# rhd_board.net
KiCad netlist of a schematic drawn in Altium Designer
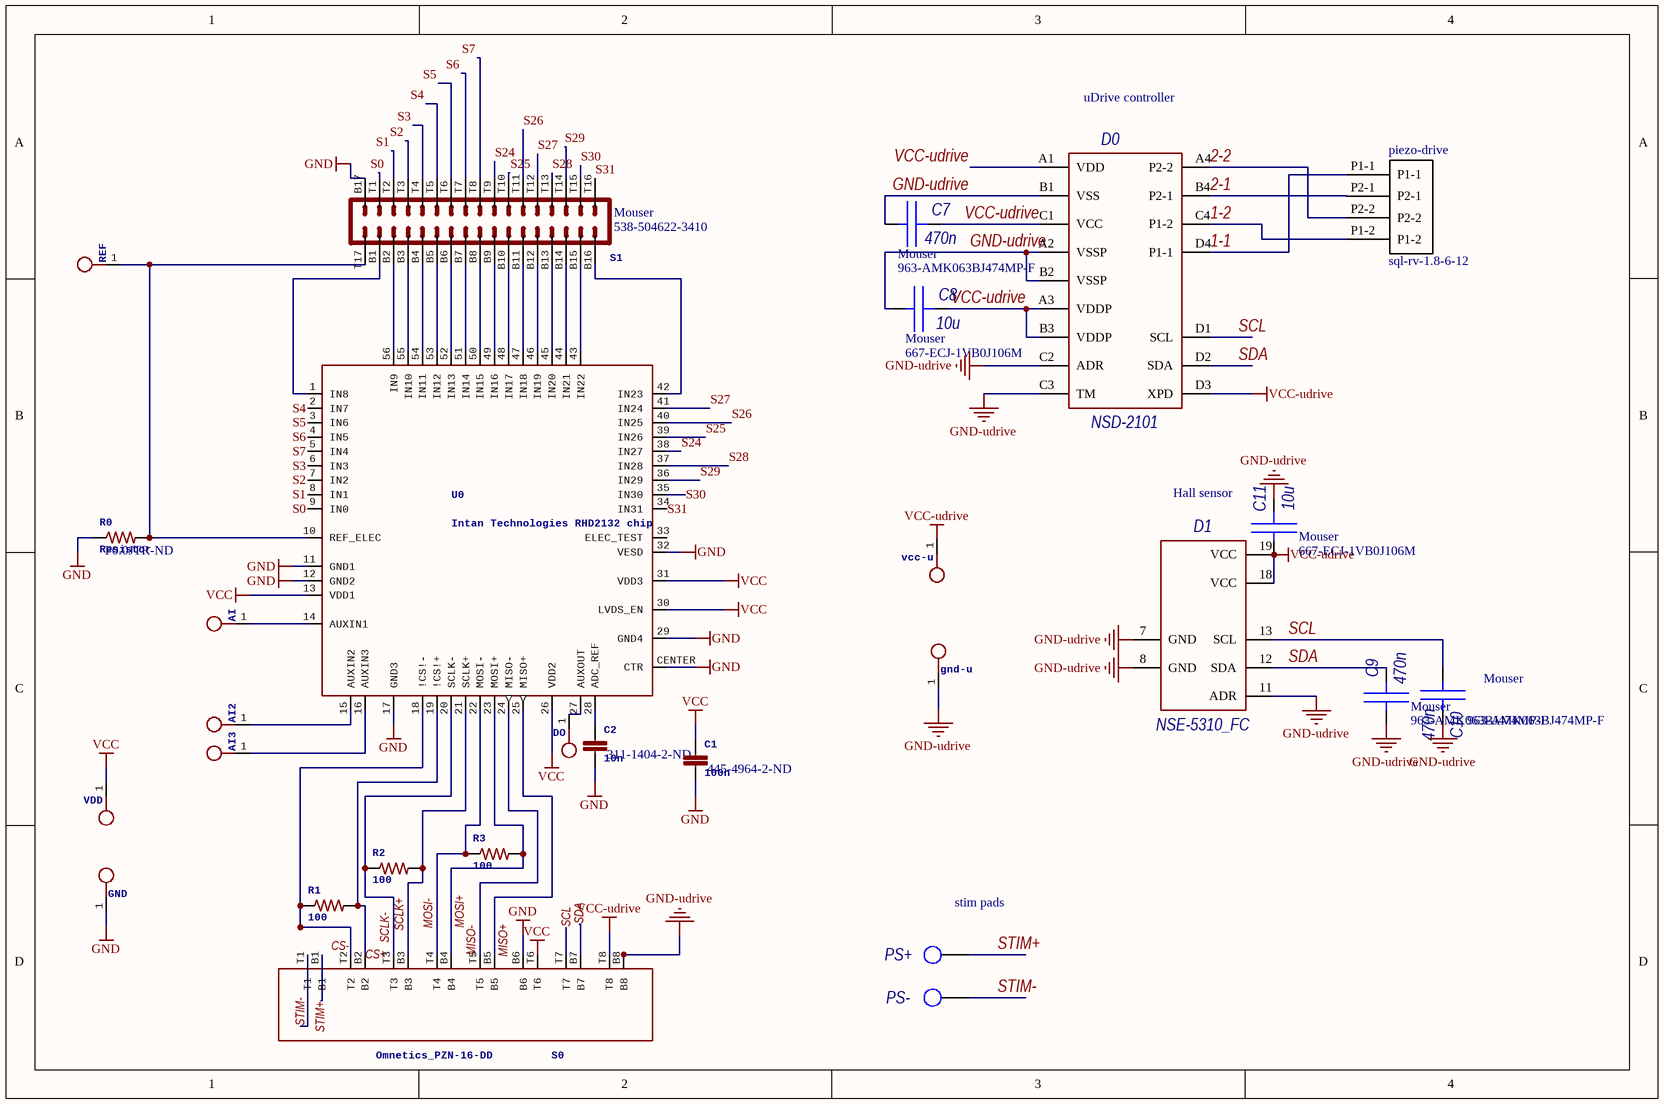
[diagram p0: rhd_board.SchDoc]

(export (version "E")
  (design (tool "Eeschema 10.0.6"))
  (components
    (comp (ref "AI")
      (value "PCB Test Point")
      (footprint "TESTPOINT_SMALL")
      (libsource (lib "RHD2000_eval_board") (part "TESTPOINT_SMALL"))
    )
    (comp (ref "AI2")
      (value "PCB Test Point")
      (footprint "TESTPOINT_SMALL")
      (libsource (lib "RHD2000_eval_board") (part "TESTPOINT_SMALL"))
    )
    (comp (ref "AI3")
      (value "PCB Test Point")
      (footprint "TESTPOINT_SMALL")
      (libsource (lib "RHD2000_eval_board") (part "TESTPOINT_SMALL"))
    )
    (comp (ref "C1")
      (value "100n")
      (footprint "0402")
      (description "ceramic capacitor (25 V). For pwer supply decoupling")
      (fields (field (name "SUPPLIER PART NUMBER 1") "445-4964-2-ND"))
      (libsource (lib "RHD2000_eval_board") (part "C_100nf"))
    )
    (comp (ref "C2")
      (value "10n")
      (footprint "0201")
      (description "ceramic 16v")
      (fields (field (name "SUPPLIER PART NUMBER 1") "311-1404-2-ND"))
      (libsource (lib "RHD2000_eval_board") (part "C_10nF"))
    )
    (comp (ref "C7")
      (value "470n")
      (footprint "CAPC0603X03L")
      (description "Capacitor")
      (fields
        (field (name "SUPPLIER 1") "Mouser")
        (field (name "SUPPLIER PART NUMBER 1") "963-AMK063BJ474MP-F")
        (field (name "PUBLISHER") "RVS")
      )
      (libsource (lib "Microdrive_Drive") (part "Cap-603"))
    )
    (comp (ref "C8")
      (value "10u")
      (footprint "CAPC1608X09L")
      (description "Capacitor")
      (fields
        (field (name "SUPPLIER 1") "Mouser")
        (field (name "SUPPLIER PART NUMBER 1") "667-ECJ-1VB0J106M")
        (field (name "PUBLISHER") "RVS")
      )
      (libsource (lib "Microdrive_Drive") (part "Cap-1608"))
    )
    (comp (ref "C9")
      (value "470n")
      (footprint "CAPC0603X03L")
      (description "Capacitor")
      (fields
        (field (name "SUPPLIER 1") "Mouser")
        (field (name "SUPPLIER PART NUMBER 1") "963-AMK063BJ474MP-F")
        (field (name "PUBLISHER") "RVS")
      )
      (libsource (lib "Microdrive_Drive") (part "Cap-603"))
    )
    (comp (ref "C10")
      (value "470n")
      (footprint "CAPC0603X03L")
      (description "Capacitor")
      (fields
        (field (name "SUPPLIER 1") "Mouser")
        (field (name "SUPPLIER PART NUMBER 1") "963-AMK063BJ474MP-F")
        (field (name "PUBLISHER") "RVS")
      )
      (libsource (lib "Microdrive_Drive") (part "Cap-603"))
    )
    (comp (ref "C11")
      (value "10u")
      (footprint "CAPC1608X09L")
      (description "Capacitor")
      (fields
        (field (name "SUPPLIER 1") "Mouser")
        (field (name "SUPPLIER PART NUMBER 1") "667-ECJ-1VB0J106M")
        (field (name "PUBLISHER") "RVS")
      )
      (libsource (lib "Microdrive_Drive") (part "Cap-1608"))
    )
    (comp (ref "D0")
      (value "NSD-2101")
      (footprint "BGA16C40P4X4_175X175X63")
      (libsource (lib "Microdrive_Drive") (part "NSD-2101"))
    )
    (comp (ref "D1")
      (value "NSE-5310_FC")
      (footprint "NSE-5310_FC")
      (libsource (lib "Microdrive_Drive") (part "NSE-5310_FC"))
    )
    (comp (ref "DO")
      (value "PCB Test Point")
      (footprint "TESTPOINT_SMALL")
      (libsource (lib "RHD2000_eval_board") (part "TESTPOINT_SMALL"))
    )
    (comp (ref "GND")
      (value "PCB Test Point")
      (footprint "TESTPOINT_SMALL")
      (libsource (lib "RHD2000_eval_board") (part "TESTPOINT_SMALL"))
    )
    (comp (ref "gnd-u")
      (value "PCB Test Point")
      (footprint "TESTPOINT_SMALL")
      (libsource (lib "RHD2000_eval_board") (part "TESTPOINT_SMALL"))
    )
    (comp (ref "piezo-drive")
      (value "sql-rv-1.8-6-12")
      (footprint "sql-rv-1.8-6-12")
      (description "Squiggle motor")
      (libsource (lib "Microdrive_Drive") (part "sql-rv-1.8-6-12"))
    )
    (comp (ref "PS+")
      (value "2-2")
      (footprint "KP-025-04")
      (libsource (lib "Microdrive_Drive") (part "KP-025X04"))
    )
    (comp (ref "PS-")
      (value "2-2")
      (footprint "KP-025-04")
      (libsource (lib "Microdrive_Drive") (part "KP-025X04"))
    )
    (comp (ref "R0")
      (value "Resistor")
      (footprint "0402")
      (description "resistor 0ohm")
      (fields (field (name "SUPPLIER PART NUMBER 1") "P0.0JTR-ND"))
      (libsource (lib "RHD2000_eval_board") (part "R_0ohm"))
    )
    (comp (ref "R1")
      (value "100")
      (footprint "0201")
      (description "100ohm resistor for lvds pair in 64ch")
      (libsource (lib "RHD2000_eval_board") (part "R_100_LVDS"))
    )
    (comp (ref "R2")
      (value "100")
      (footprint "0201")
      (description "100ohm resistor for lvds pair in 64ch")
      (libsource (lib "RHD2000_eval_board") (part "R_100_LVDS"))
    )
    (comp (ref "R3")
      (value "100")
      (footprint "0201")
      (description "100ohm resistor for lvds pair in 64ch")
      (libsource (lib "RHD2000_eval_board") (part "R_100_LVDS"))
    )
    (comp (ref "REF")
      (value "PCB Test Point")
      (footprint "TESTPOINT_SMALL")
      (libsource (lib "RHD2000_eval_board") (part "TESTPOINT_SMALL"))
    )
    (comp (ref "S0")
      (value "Omnetics_PZN-16-DD")
      (footprint "OMNETICS_PZN-16-DD")
      (libsource (lib "RHD2000_eval_board") (part "Omnetics_PZN-16-DD"))
    )
    (comp (ref "S1")
      (value "Molex 3.5mm Pitch Slimstack 34 pin connector")
      (footprint "MOLEX_504622-3412")
      (fields (field (name "SUPPLIER 1") "Mouser") (field (name "SUPPLIER PART NUMBER 1") "538-504622-3410"))
      (libsource (lib "Microdrive_Drive") (part "MOLEX_504622-3412"))
    )
    (comp (ref "U0")
      (value "Intan Technologies RHD2132 chip")
      (footprint "RHD2000_56PIN_COB")
      (libsource (lib "RHD2000") (part "RHD2132_COB"))
    )
    (comp (ref "vcc-u")
      (value "PCB Test Point")
      (footprint "TESTPOINT_SMALL")
      (libsource (lib "RHD2000_eval_board") (part "TESTPOINT_SMALL"))
    )
    (comp (ref "VDD")
      (value "PCB Test Point")
      (footprint "TESTPOINT_SMALL")
      (libsource (lib "RHD2000_eval_board") (part "TESTPOINT_SMALL"))
    )
  )
  (nets
    (net (code "1") (name "/1-1") (class "Default")
      (node (ref "D0") (pin "D4") (pinfunction "P1-1_D4") (pintype "passive"))
      (node (ref "piezo-drive") (pin "P1-1") (pinfunction "P1-1_P1-1") (pintype "passive"))
    )
    (net (code "2") (name "/1-2") (class "Default")
      (node (ref "D0") (pin "C4") (pinfunction "P1-2_C4") (pintype "passive"))
      (node (ref "piezo-drive") (pin "P1-2") (pinfunction "P1-2_P1-2") (pintype "passive"))
    )
    (net (code "3") (name "/2-1") (class "Default")
      (node (ref "D0") (pin "B4") (pinfunction "P2-1_B4") (pintype "passive"))
      (node (ref "piezo-drive") (pin "P2-1") (pinfunction "P2-1_P2-1") (pintype "passive"))
    )
    (net (code "4") (name "/2-2") (class "Default")
      (node (ref "D0") (pin "A4") (pinfunction "P2-2_A4") (pintype "passive"))
      (node (ref "piezo-drive") (pin "P2-2") (pinfunction "P2-2_P2-2") (pintype "passive"))
    )
    (net (code "5") (name "/CS+") (class "Default")
      (node (ref "R1") (pin "2") (pinfunction "2_2") (pintype "passive"))
      (node (ref "S0") (pin "B2") (pinfunction "B2_B2") (pintype "passive"))
      (node (ref "U0") (pin "19") (pinfunction "!CS!+_19") (pintype "passive"))
    )
    (net (code "6") (name "/CS-") (class "Default")
      (node (ref "R1") (pin "1") (pinfunction "1_1") (pintype "passive"))
      (node (ref "S0") (pin "T2") (pinfunction "T2_T2") (pintype "passive"))
      (node (ref "U0") (pin "18") (pinfunction "!CS!-_18") (pintype "passive"))
    )
    (net (code "7") (name "/MISO+") (class "Default")
      (node (ref "S0") (pin "B5") (pinfunction "B5_B5") (pintype "passive"))
      (node (ref "U0") (pin "25") (pinfunction "MISO+_25") (pintype "output"))
    )
    (net (code "8") (name "/MISO-") (class "Default")
      (node (ref "S0") (pin "T5") (pinfunction "T5_T5") (pintype "passive"))
      (node (ref "U0") (pin "24") (pinfunction "MISO-_24") (pintype "output"))
    )
    (net (code "9") (name "/MOSI+") (class "Default")
      (node (ref "R3") (pin "2") (pinfunction "2_2") (pintype "passive"))
      (node (ref "S0") (pin "B4") (pinfunction "B4_B4") (pintype "passive"))
      (node (ref "U0") (pin "23") (pinfunction "MOSI+_23") (pintype "passive"))
    )
    (net (code "10") (name "/MOSI-") (class "Default")
      (node (ref "R3") (pin "1") (pinfunction "1_1") (pintype "passive"))
      (node (ref "S0") (pin "T4") (pinfunction "T4_T4") (pintype "passive"))
      (node (ref "U0") (pin "22") (pinfunction "MOSI-_22") (pintype "passive"))
    )
    (net (code "11") (name "/S0") (class "Default")
      (node (ref "S1") (pin "T1") (pinfunction "T1_T1") (pintype "passive"))
      (node (ref "U0") (pin "9") (pinfunction "IN0_9") (pintype "passive"))
    )
    (net (code "12") (name "/S1") (class "Default")
      (node (ref "S1") (pin "T2") (pinfunction "T2_T2") (pintype "passive"))
      (node (ref "U0") (pin "8") (pinfunction "IN1_8") (pintype "passive"))
    )
    (net (code "13") (name "/S2") (class "Default")
      (node (ref "S1") (pin "T3") (pinfunction "T3_T3") (pintype "passive"))
      (node (ref "U0") (pin "7") (pinfunction "IN2_7") (pintype "passive"))
    )
    (net (code "14") (name "/S3") (class "Default")
      (node (ref "S1") (pin "T4") (pinfunction "T4_T4") (pintype "passive"))
      (node (ref "U0") (pin "6") (pinfunction "IN3_6") (pintype "passive"))
    )
    (net (code "15") (name "/S4") (class "Default")
      (node (ref "S1") (pin "T5") (pinfunction "T5_T5") (pintype "passive"))
      (node (ref "U0") (pin "2") (pinfunction "IN7_2") (pintype "passive"))
    )
    (net (code "16") (name "/S5") (class "Default")
      (node (ref "S1") (pin "T6") (pinfunction "T6_T6") (pintype "passive"))
      (node (ref "U0") (pin "3") (pinfunction "IN6_3") (pintype "passive"))
    )
    (net (code "17") (name "/S6") (class "Default")
      (node (ref "S1") (pin "T7") (pinfunction "T7_T7") (pintype "passive"))
      (node (ref "U0") (pin "4") (pinfunction "IN5_4") (pintype "passive"))
    )
    (net (code "18") (name "/S7") (class "Default")
      (node (ref "S1") (pin "T8") (pinfunction "T8_T8") (pintype "passive"))
      (node (ref "U0") (pin "5") (pinfunction "IN4_5") (pintype "passive"))
    )
    (net (code "19") (name "/S24") (class "Default")
      (node (ref "S1") (pin "T9") (pinfunction "T9_T9") (pintype "passive"))
      (node (ref "U0") (pin "38") (pinfunction "IN27_38") (pintype "passive"))
    )
    (net (code "20") (name "/S25") (class "Default")
      (node (ref "S1") (pin "T10") (pinfunction "T10_T10") (pintype "passive"))
      (node (ref "U0") (pin "39") (pinfunction "IN26_39") (pintype "passive"))
    )
    (net (code "21") (name "/S26") (class "Default")
      (node (ref "S1") (pin "T11") (pinfunction "T11_T11") (pintype "passive"))
      (node (ref "U0") (pin "40") (pinfunction "IN25_40") (pintype "passive"))
    )
    (net (code "22") (name "/S27") (class "Default")
      (node (ref "S1") (pin "T12") (pinfunction "T12_T12") (pintype "passive"))
      (node (ref "U0") (pin "41") (pinfunction "IN24_41") (pintype "passive"))
    )
    (net (code "23") (name "/S28") (class "Default")
      (node (ref "S1") (pin "T13") (pinfunction "T13_T13") (pintype "passive"))
      (node (ref "U0") (pin "37") (pinfunction "IN28_37") (pintype "passive"))
    )
    (net (code "24") (name "/S29") (class "Default")
      (node (ref "S1") (pin "T14") (pinfunction "T14_T14") (pintype "passive"))
      (node (ref "U0") (pin "36") (pinfunction "IN29_36") (pintype "passive"))
    )
    (net (code "25") (name "/S30") (class "Default")
      (node (ref "S1") (pin "T15") (pinfunction "T15_T15") (pintype "passive"))
      (node (ref "U0") (pin "35") (pinfunction "IN30_35") (pintype "passive"))
    )
    (net (code "26") (name "/S31") (class "Default")
      (node (ref "S1") (pin "T16") (pinfunction "T16_T16") (pintype "passive"))
      (node (ref "U0") (pin "34") (pinfunction "IN31_34") (pintype "passive"))
    )
    (net (code "27") (name "/SCL") (class "Default")
      (node (ref "C10") (pin "1") (pinfunction "1_1") (pintype "passive"))
      (node (ref "D0") (pin "D1") (pinfunction "SCL_D1") (pintype "passive"))
      (node (ref "D1") (pin "13") (pinfunction "SCL_13") (pintype "passive"))
      (node (ref "S0") (pin "T7") (pinfunction "T7_T7") (pintype "passive"))
    )
    (net (code "28") (name "/SCLK+") (class "Default")
      (node (ref "R2") (pin "2") (pinfunction "2_2") (pintype "passive"))
      (node (ref "S0") (pin "B3") (pinfunction "B3_B3") (pintype "passive"))
      (node (ref "U0") (pin "21") (pinfunction "SCLK+_21") (pintype "passive"))
    )
    (net (code "29") (name "/SCLK-") (class "Default")
      (node (ref "R2") (pin "1") (pinfunction "1_1") (pintype "passive"))
      (node (ref "S0") (pin "T3") (pinfunction "T3_T3") (pintype "passive"))
      (node (ref "U0") (pin "20") (pinfunction "SCLK-_20") (pintype "passive"))
    )
    (net (code "30") (name "/SDA") (class "Default")
      (node (ref "C9") (pin "2") (pinfunction "2_2") (pintype "passive"))
      (node (ref "D0") (pin "D2") (pinfunction "SDA_D2") (pintype "passive"))
      (node (ref "D1") (pin "12") (pinfunction "SDA_12") (pintype "passive"))
      (node (ref "S0") (pin "B7") (pinfunction "B7_B7") (pintype "passive"))
    )
    (net (code "31") (name "/STIM+") (class "Default")
      (node (ref "PS+") (pin "1") (pinfunction "1_1") (pintype "passive"))
      (node (ref "S0") (pin "B1") (pinfunction "B1_B1") (pintype "passive"))
    )
    (net (code "32") (name "/STIM-") (class "Default")
      (node (ref "PS-") (pin "1") (pinfunction "1_1") (pintype "passive"))
      (node (ref "S0") (pin "T1") (pinfunction "T1_T1") (pintype "passive"))
    )
    (net (code "33") (name "GND") (class "Default")
      (node (ref "C1") (pin "2") (pinfunction "2_2") (pintype "passive"))
      (node (ref "C2") (pin "2") (pinfunction "2_2") (pintype "passive"))
      (node (ref "GND") (pin "1") (pinfunction "1_1") (pintype "passive"))
      (node (ref "R0") (pin "1") (pinfunction "1_1") (pintype "passive"))
      (node (ref "S0") (pin "B6") (pinfunction "B6_B6") (pintype "passive"))
      (node (ref "S1") (pin "B17") (pinfunction "B17_B17") (pintype "passive"))
      (node (ref "U0") (pin "11") (pinfunction "GND1_11") (pintype "power_in"))
      (node (ref "U0") (pin "12") (pinfunction "GND2_12") (pintype "power_in"))
      (node (ref "U0") (pin "17") (pinfunction "GND3_17") (pintype "power_in"))
      (node (ref "U0") (pin "29") (pinfunction "GND4_29") (pintype "power_in"))
      (node (ref "U0") (pin "32") (pinfunction "VESD_32") (pintype "power_in"))
      (node (ref "U0") (pin "CENTER") (pinfunction "CTR_CENTER") (pintype "power_in"))
    )
    (net (code "34") (name "GND-udrive") (class "Default")
      (node (ref "C10") (pin "2") (pinfunction "2_2") (pintype "passive"))
      (node (ref "C11") (pin "2") (pinfunction "2_2") (pintype "passive"))
      (node (ref "C7") (pin "1") (pinfunction "1_1") (pintype "passive"))
      (node (ref "C8") (pin "1") (pinfunction "1_1") (pintype "passive"))
      (node (ref "C9") (pin "1") (pinfunction "1_1") (pintype "passive"))
      (node (ref "D0") (pin "A2") (pinfunction "VSSP_A2") (pintype "passive"))
      (node (ref "D0") (pin "B1") (pinfunction "VSS_B1") (pintype "passive"))
      (node (ref "D0") (pin "B2") (pinfunction "VSSP_B2") (pintype "passive"))
      (node (ref "D0") (pin "C2") (pinfunction "ADR_C2") (pintype "passive"))
      (node (ref "D0") (pin "C3") (pinfunction "TM_C3") (pintype "passive"))
      (node (ref "D1") (pin "11") (pinfunction "ADR_11") (pintype "passive"))
      (node (ref "D1") (pin "7") (pinfunction "GND_7") (pintype "passive"))
      (node (ref "D1") (pin "8") (pinfunction "GND_8") (pintype "passive"))
      (node (ref "S0") (pin "B8") (pinfunction "B8_B8") (pintype "passive"))
      (node (ref "gnd-u") (pin "1") (pinfunction "1_1") (pintype "passive"))
    )
    (net (code "35") (name "Net-(U0-ADC_REF)") (class "Default")
      (node (ref "C2") (pin "1") (pinfunction "1_1") (pintype "passive"))
      (node (ref "U0") (pin "28") (pinfunction "ADC_REF_28") (pintype "passive"))
    )
    (net (code "36") (name "Net-(U0-AUXIN1)") (class "Default")
      (node (ref "AI") (pin "1") (pinfunction "1_1") (pintype "passive"))
      (node (ref "U0") (pin "14") (pinfunction "AUXIN1_14") (pintype "passive"))
    )
    (net (code "37") (name "Net-(U0-AUXIN2)") (class "Default")
      (node (ref "AI2") (pin "1") (pinfunction "1_1") (pintype "passive"))
      (node (ref "U0") (pin "15") (pinfunction "AUXIN2_15") (pintype "passive"))
    )
    (net (code "38") (name "Net-(U0-AUXIN3)") (class "Default")
      (node (ref "AI3") (pin "1") (pinfunction "1_1") (pintype "passive"))
      (node (ref "U0") (pin "16") (pinfunction "AUXIN3_16") (pintype "passive"))
    )
    (net (code "39") (name "Net-(U0-AUXOUT)") (class "Default")
      (node (ref "DO") (pin "1") (pinfunction "1_1") (pintype "passive"))
      (node (ref "U0") (pin "27") (pinfunction "AUXOUT_27") (pintype "tri_state"))
    )
    (net (code "40") (name "Net-(U0-IN8)") (class "Default")
      (node (ref "S1") (pin "B1") (pinfunction "B1_B1") (pintype "passive"))
      (node (ref "U0") (pin "1") (pinfunction "IN8_1") (pintype "passive"))
    )
    (net (code "41") (name "Net-(U0-IN9)") (class "Default")
      (node (ref "S1") (pin "B2") (pinfunction "B2_B2") (pintype "passive"))
      (node (ref "U0") (pin "56") (pinfunction "IN9_56") (pintype "passive"))
    )
    (net (code "42") (name "Net-(U0-IN10)") (class "Default")
      (node (ref "S1") (pin "B3") (pinfunction "B3_B3") (pintype "passive"))
      (node (ref "U0") (pin "55") (pinfunction "IN10_55") (pintype "passive"))
    )
    (net (code "43") (name "Net-(U0-IN11)") (class "Default")
      (node (ref "S1") (pin "B4") (pinfunction "B4_B4") (pintype "passive"))
      (node (ref "U0") (pin "54") (pinfunction "IN11_54") (pintype "passive"))
    )
    (net (code "44") (name "Net-(U0-IN12)") (class "Default")
      (node (ref "S1") (pin "B5") (pinfunction "B5_B5") (pintype "passive"))
      (node (ref "U0") (pin "53") (pinfunction "IN12_53") (pintype "passive"))
    )
    (net (code "45") (name "Net-(U0-IN13)") (class "Default")
      (node (ref "S1") (pin "B6") (pinfunction "B6_B6") (pintype "passive"))
      (node (ref "U0") (pin "52") (pinfunction "IN13_52") (pintype "passive"))
    )
    (net (code "46") (name "Net-(U0-IN14)") (class "Default")
      (node (ref "S1") (pin "B7") (pinfunction "B7_B7") (pintype "passive"))
      (node (ref "U0") (pin "51") (pinfunction "IN14_51") (pintype "passive"))
    )
    (net (code "47") (name "Net-(U0-IN15)") (class "Default")
      (node (ref "S1") (pin "B8") (pinfunction "B8_B8") (pintype "passive"))
      (node (ref "U0") (pin "50") (pinfunction "IN15_50") (pintype "passive"))
    )
    (net (code "48") (name "Net-(U0-IN16)") (class "Default")
      (node (ref "S1") (pin "B9") (pinfunction "B9_B9") (pintype "passive"))
      (node (ref "U0") (pin "49") (pinfunction "IN16_49") (pintype "passive"))
    )
    (net (code "49") (name "Net-(U0-IN17)") (class "Default")
      (node (ref "S1") (pin "B10") (pinfunction "B10_B10") (pintype "passive"))
      (node (ref "U0") (pin "48") (pinfunction "IN17_48") (pintype "passive"))
    )
    (net (code "50") (name "Net-(U0-IN18)") (class "Default")
      (node (ref "S1") (pin "B11") (pinfunction "B11_B11") (pintype "passive"))
      (node (ref "U0") (pin "47") (pinfunction "IN18_47") (pintype "passive"))
    )
    (net (code "51") (name "Net-(U0-IN19)") (class "Default")
      (node (ref "S1") (pin "B12") (pinfunction "B12_B12") (pintype "passive"))
      (node (ref "U0") (pin "46") (pinfunction "IN19_46") (pintype "passive"))
    )
    (net (code "52") (name "Net-(U0-IN20)") (class "Default")
      (node (ref "S1") (pin "B13") (pinfunction "B13_B13") (pintype "passive"))
      (node (ref "U0") (pin "45") (pinfunction "IN20_45") (pintype "passive"))
    )
    (net (code "53") (name "Net-(U0-IN21)") (class "Default")
      (node (ref "S1") (pin "B14") (pinfunction "B14_B14") (pintype "passive"))
      (node (ref "U0") (pin "44") (pinfunction "IN21_44") (pintype "passive"))
    )
    (net (code "54") (name "Net-(U0-IN22)") (class "Default")
      (node (ref "S1") (pin "B15") (pinfunction "B15_B15") (pintype "passive"))
      (node (ref "U0") (pin "43") (pinfunction "IN22_43") (pintype "passive"))
    )
    (net (code "55") (name "Net-(U0-IN23)") (class "Default")
      (node (ref "S1") (pin "B16") (pinfunction "B16_B16") (pintype "passive"))
      (node (ref "U0") (pin "42") (pinfunction "IN23_42") (pintype "passive"))
    )
    (net (code "56") (name "Net-(U0-REF_ELEC)") (class "Default")
      (node (ref "R0") (pin "2") (pinfunction "2_2") (pintype "passive"))
      (node (ref "REF") (pin "1") (pinfunction "1_1") (pintype "passive"))
      (node (ref "S1") (pin "T17") (pinfunction "T17_T17") (pintype "passive"))
      (node (ref "U0") (pin "10") (pinfunction "REF_ELEC_10") (pintype "passive"))
    )
    (net (code "57") (name "VCC") (class "Default")
      (node (ref "C1") (pin "1") (pinfunction "1_1") (pintype "passive"))
      (node (ref "S0") (pin "T6") (pinfunction "T6_T6") (pintype "passive"))
      (node (ref "U0") (pin "13") (pinfunction "VDD1_13") (pintype "power_in"))
      (node (ref "U0") (pin "26") (pinfunction "VDD2_26") (pintype "power_in"))
      (node (ref "U0") (pin "30") (pinfunction "LVDS_EN_30") (pintype "passive"))
      (node (ref "U0") (pin "31") (pinfunction "VDD3_31") (pintype "power_in"))
      (node (ref "VDD") (pin "1") (pinfunction "1_1") (pintype "passive"))
    )
    (net (code "58") (name "VCC-udrive") (class "Default")
      (node (ref "C11") (pin "1") (pinfunction "1_1") (pintype "passive"))
      (node (ref "C7") (pin "2") (pinfunction "2_2") (pintype "passive"))
      (node (ref "C8") (pin "2") (pinfunction "2_2") (pintype "passive"))
      (node (ref "D0") (pin "A1") (pinfunction "VDD_A1") (pintype "passive"))
      (node (ref "D0") (pin "A3") (pinfunction "VDDP_A3") (pintype "passive"))
      (node (ref "D0") (pin "B3") (pinfunction "VDDP_B3") (pintype "passive"))
      (node (ref "D0") (pin "C1") (pinfunction "VCC_C1") (pintype "passive"))
      (node (ref "D0") (pin "D3") (pinfunction "XPD_D3") (pintype "passive"))
      (node (ref "D1") (pin "18") (pinfunction "VCC_18") (pintype "passive"))
      (node (ref "D1") (pin "19") (pinfunction "VCC_19") (pintype "passive"))
      (node (ref "S0") (pin "T8") (pinfunction "T8_T8") (pintype "passive"))
      (node (ref "vcc-u") (pin "1") (pinfunction "1_1") (pintype "passive"))
    )
    (net (code "59") (name "unconnected-(U0-ELEC_TEST-Pad33)") (class "Default")
      (node (ref "U0") (pin "33") (pinfunction "ELEC_TEST_33") (pintype "passive"))
    )
  )
)
